# sch.net
KiCad netlist of a schematic drawn in Altium Designer
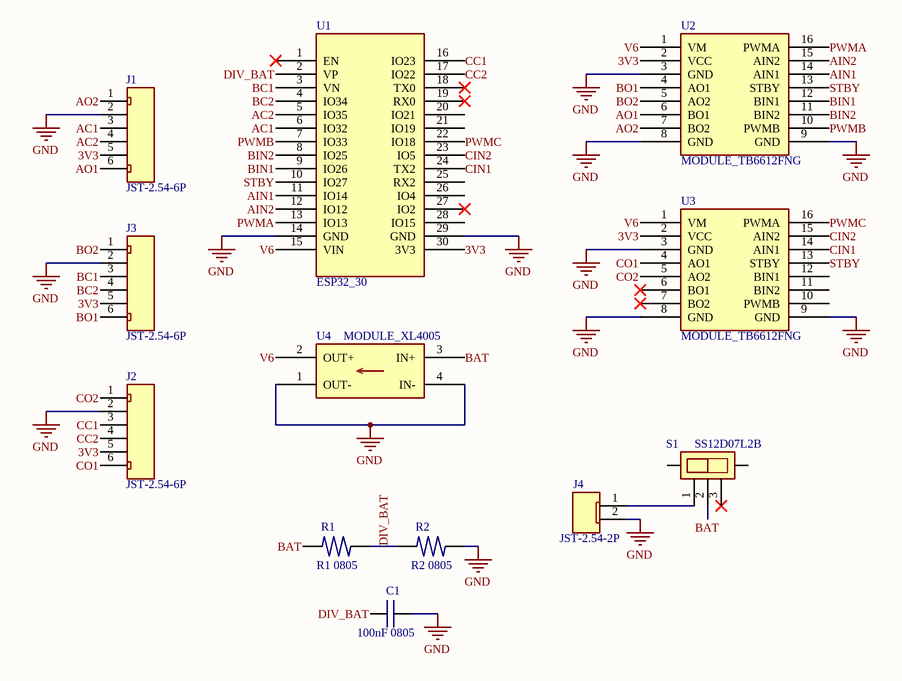
[diagram p0: sch.SchDoc]

(export (version "E")
  (design (tool "Eeschema 10.0.6"))
  (components
    (comp (ref "C1")
      (value "100nF 0805")
      (footprint "CAPACITOR 0805")
      (description "Generic Capacitor 0805, 2x1.25x1.4mm.")
      (libsource (lib "Ceramic Capacitor") (part "CAPACITOR 0805"))
    )
    (comp (ref "J1")
      (value "JST-2.54-6P")
      (footprint "JST-2.54-6P")
      (description "Female Connector JST 6 Vias, 2.54mm.")
      (libsource (lib "Connectors") (part "JST-2.54-6P"))
    )
    (comp (ref "J2")
      (value "JST-2.54-6P")
      (footprint "JST-2.54-6P")
      (description "Female Connector JST 6 Vias, 2.54mm.")
      (libsource (lib "Connectors") (part "JST-2.54-6P"))
    )
    (comp (ref "J3")
      (value "JST-2.54-6P")
      (footprint "JST-2.54-6P")
      (description "Female Connector JST 6 Vias, 2.54mm.")
      (libsource (lib "Connectors") (part "JST-2.54-6P"))
    )
    (comp (ref "J4")
      (value "JST-2.54-2P")
      (footprint "JST-2.54-2P")
      (description "Female Connector JST 2 Vias, 2.54mm.")
      (libsource (lib "Connectors") (part "JST-2.54-2P"))
    )
    (comp (ref "R1")
      (value "R1 0805")
      (footprint "RESISTOR_0805")
      (libsource (lib "Resistors") (part "RESISTOR_0805"))
    )
    (comp (ref "R2")
      (value "R2 0805")
      (footprint "RESISTOR_0805")
      (libsource (lib "Resistors") (part "RESISTOR_0805"))
    )
    (comp (ref "S1")
      (value "SS12D07L2B")
      (footprint "SS12D07L2B")
      (description "Vertical Slide Switch 5 Pins 8.7x4.5x4.7mm.")
      (libsource (lib "Buttons & Switches") (part "SS12D07L2B"))
    )
    (comp (ref "U1")
      (value "ESP32_30")
      (footprint "ESP32_30")
      (description "Microcontoller Board 30 Pins Wifi 2.4GHz BLE 4.2 ESP32-WROOM-32D")
      (libsource (lib "Espressif Microcontrollers") (part "ESP32_30"))
    )
    (comp (ref "U2")
      (value "MODULE_TB6612FNG")
      (footprint "MODULE_TB6612FNG")
      (description "Module Dual Motor Driver 2.5-13.5V 3.2A Peak 21x18mm")
      (libsource (lib "Motor Drivers") (part "MODULE_TB6612FNG"))
    )
    (comp (ref "U3")
      (value "MODULE_TB6612FNG")
      (footprint "MODULE_TB6612FNG")
      (description "Module Dual Motor Driver 2.5-13.5V 3.2A Peak 21x18mm")
      (libsource (lib "Motor Drivers") (part "MODULE_TB6612FNG"))
    )
    (comp (ref "U4")
      (value "MODULE_XL4005")
      (footprint "MODULE_XL4005")
      (description "MODULE BUCK STEP DOWN 5A 44x21mm")
      (libsource (lib "Voltage Regulators") (part "MODULE_XL4005"))
    )
  )
  (nets
    (net (code "1") (name "/3V3") (class "Default")
      (node (ref "J1") (pin "5") (pintype "passive"))
      (node (ref "J2") (pin "5") (pintype "passive"))
      (node (ref "J3") (pin "5") (pintype "passive"))
      (node (ref "U1") (pin "30") (pinfunction "3V3_30") (pintype "passive"))
      (node (ref "U2") (pin "2") (pinfunction "VCC_2") (pintype "passive"))
      (node (ref "U3") (pin "2") (pinfunction "VCC_2") (pintype "passive"))
    )
    (net (code "2") (name "/AC1") (class "Default")
      (node (ref "J1") (pin "3") (pintype "passive"))
      (node (ref "U1") (pin "6") (pinfunction "IO32_6") (pintype "passive"))
    )
    (net (code "3") (name "/AC2") (class "Default")
      (node (ref "J1") (pin "4") (pintype "passive"))
      (node (ref "U1") (pin "5") (pinfunction "IO35_5") (pintype "passive"))
    )
    (net (code "4") (name "/AIN1") (class "Default")
      (node (ref "U1") (pin "11") (pinfunction "IO14_11") (pintype "passive"))
      (node (ref "U2") (pin "14") (pinfunction "AIN1_14") (pintype "passive"))
    )
    (net (code "5") (name "/AIN2") (class "Default")
      (node (ref "U1") (pin "12") (pinfunction "IO12_12") (pintype "passive"))
      (node (ref "U2") (pin "15") (pinfunction "AIN2_15") (pintype "passive"))
    )
    (net (code "6") (name "/AO1") (class "Default")
      (node (ref "J1") (pin "6") (pintype "passive"))
      (node (ref "U2") (pin "6") (pinfunction "BO1_6") (pintype "passive"))
    )
    (net (code "7") (name "/AO2") (class "Default")
      (node (ref "J1") (pin "1") (pintype "passive"))
      (node (ref "U2") (pin "7") (pinfunction "BO2_7") (pintype "passive"))
    )
    (net (code "8") (name "/BAT") (class "Default")
      (node (ref "R1") (pin "2") (pinfunction "2_2") (pintype "passive"))
      (node (ref "S1") (pin "2") (pinfunction "2_2") (pintype "passive"))
      (node (ref "U4") (pin "3") (pinfunction "IN+_3") (pintype "passive"))
    )
    (net (code "9") (name "/BC1") (class "Default")
      (node (ref "J3") (pin "3") (pintype "passive"))
      (node (ref "U1") (pin "3") (pinfunction "VN_3") (pintype "passive"))
    )
    (net (code "10") (name "/BC2") (class "Default")
      (node (ref "J3") (pin "4") (pintype "passive"))
      (node (ref "U1") (pin "4") (pinfunction "IO34_4") (pintype "passive"))
    )
    (net (code "11") (name "/BIN1") (class "Default")
      (node (ref "U1") (pin "9") (pinfunction "IO26_9") (pintype "passive"))
      (node (ref "U2") (pin "12") (pinfunction "BIN1_12") (pintype "passive"))
    )
    (net (code "12") (name "/BIN2") (class "Default")
      (node (ref "U1") (pin "8") (pinfunction "IO25_8") (pintype "passive"))
      (node (ref "U2") (pin "11") (pinfunction "BIN2_11") (pintype "passive"))
    )
    (net (code "13") (name "/BO1") (class "Default")
      (node (ref "J3") (pin "6") (pintype "passive"))
      (node (ref "U2") (pin "4") (pinfunction "AO1_4") (pintype "passive"))
    )
    (net (code "14") (name "/BO2") (class "Default")
      (node (ref "J3") (pin "1") (pintype "passive"))
      (node (ref "U2") (pin "5") (pinfunction "AO2_5") (pintype "passive"))
    )
    (net (code "15") (name "/CC1") (class "Default")
      (node (ref "J2") (pin "3") (pintype "passive"))
      (node (ref "U1") (pin "16") (pinfunction "IO23_16") (pintype "passive"))
    )
    (net (code "16") (name "/CC2") (class "Default")
      (node (ref "J2") (pin "4") (pintype "passive"))
      (node (ref "U1") (pin "17") (pinfunction "IO22_17") (pintype "passive"))
    )
    (net (code "17") (name "/CIN1") (class "Default")
      (node (ref "U1") (pin "24") (pinfunction "TX2_24") (pintype "passive"))
      (node (ref "U3") (pin "14") (pinfunction "AIN1_14") (pintype "passive"))
    )
    (net (code "18") (name "/CIN2") (class "Default")
      (node (ref "U1") (pin "23") (pinfunction "IO5_23") (pintype "passive"))
      (node (ref "U3") (pin "15") (pinfunction "AIN2_15") (pintype "passive"))
    )
    (net (code "19") (name "/CO1") (class "Default")
      (node (ref "J2") (pin "6") (pintype "passive"))
      (node (ref "U3") (pin "4") (pinfunction "AO1_4") (pintype "passive"))
    )
    (net (code "20") (name "/CO2") (class "Default")
      (node (ref "J2") (pin "1") (pintype "passive"))
      (node (ref "U3") (pin "5") (pinfunction "AO2_5") (pintype "passive"))
    )
    (net (code "21") (name "/DIV_BAT") (class "Default")
      (node (ref "C1") (pin "1") (pinfunction "1_1") (pintype "passive"))
      (node (ref "R1") (pin "1") (pinfunction "1_1") (pintype "passive"))
      (node (ref "R2") (pin "2") (pinfunction "2_2") (pintype "passive"))
      (node (ref "U1") (pin "2") (pinfunction "VP_2") (pintype "passive"))
    )
    (net (code "22") (name "/PWMA") (class "Default")
      (node (ref "U1") (pin "13") (pinfunction "IO13_13") (pintype "passive"))
      (node (ref "U2") (pin "16") (pinfunction "PWMA_16") (pintype "passive"))
    )
    (net (code "23") (name "/PWMB") (class "Default")
      (node (ref "U1") (pin "7") (pinfunction "IO33_7") (pintype "passive"))
      (node (ref "U2") (pin "10") (pinfunction "PWMB_10") (pintype "passive"))
    )
    (net (code "24") (name "/PWMC") (class "Default")
      (node (ref "U1") (pin "22") (pinfunction "IO18_22") (pintype "passive"))
      (node (ref "U3") (pin "16") (pinfunction "PWMA_16") (pintype "passive"))
    )
    (net (code "25") (name "/STBY") (class "Default")
      (node (ref "U1") (pin "10") (pinfunction "IO27_10") (pintype "passive"))
      (node (ref "U2") (pin "13") (pinfunction "STBY_13") (pintype "passive"))
      (node (ref "U3") (pin "13") (pinfunction "STBY_13") (pintype "passive"))
    )
    (net (code "26") (name "/V6") (class "Default")
      (node (ref "U1") (pin "15") (pinfunction "VIN_15") (pintype "passive"))
      (node (ref "U2") (pin "1") (pinfunction "VM_1") (pintype "passive"))
      (node (ref "U3") (pin "1") (pinfunction "VM_1") (pintype "passive"))
      (node (ref "U4") (pin "2") (pinfunction "OUT+_2") (pintype "passive"))
    )
    (net (code "27") (name "GND") (class "Default")
      (node (ref "C1") (pin "2") (pinfunction "2_2") (pintype "passive"))
      (node (ref "J1") (pin "2") (pintype "passive"))
      (node (ref "J2") (pin "2") (pintype "passive"))
      (node (ref "J3") (pin "2") (pintype "passive"))
      (node (ref "J4") (pin "2") (pintype "passive"))
      (node (ref "R2") (pin "1") (pinfunction "1_1") (pintype "passive"))
      (node (ref "U1") (pin "14") (pinfunction "GND_14") (pintype "passive"))
      (node (ref "U1") (pin "29") (pinfunction "GND_29") (pintype "passive"))
      (node (ref "U2") (pin "3") (pinfunction "GND_3") (pintype "passive"))
      (node (ref "U2") (pin "8") (pinfunction "GND_8") (pintype "passive"))
      (node (ref "U2") (pin "9") (pinfunction "GND_9") (pintype "passive"))
      (node (ref "U3") (pin "3") (pinfunction "GND_3") (pintype "passive"))
      (node (ref "U3") (pin "8") (pinfunction "GND_8") (pintype "passive"))
      (node (ref "U3") (pin "9") (pinfunction "GND_9") (pintype "passive"))
      (node (ref "U4") (pin "1") (pinfunction "OUT-_1") (pintype "passive"))
      (node (ref "U4") (pin "4") (pinfunction "IN-_4") (pintype "passive"))
    )
    (net (code "28") (name "Net-(J4-Pad1)") (class "Default")
      (node (ref "J4") (pin "1") (pintype "passive"))
      (node (ref "S1") (pin "1") (pinfunction "1_1") (pintype "passive"))
    )
    (net (code "29") (name "unconnected-(S1-Pad3)") (class "Default")
      (node (ref "S1") (pin "3") (pinfunction "3_3") (pintype "passive+no_connect"))
    )
    (net (code "30") (name "unconnected-(U1-EN-Pad1)") (class "Default")
      (node (ref "U1") (pin "1") (pinfunction "EN_1") (pintype "passive+no_connect"))
    )
    (net (code "31") (name "unconnected-(U1-IO2-Pad27)") (class "Default")
      (node (ref "U1") (pin "27") (pinfunction "IO2_27") (pintype "passive+no_connect"))
    )
    (net (code "32") (name "unconnected-(U1-IO4-Pad26)") (class "Default")
      (node (ref "U1") (pin "26") (pinfunction "IO4_26") (pintype "passive"))
    )
    (net (code "33") (name "unconnected-(U1-IO15-Pad28)") (class "Default")
      (node (ref "U1") (pin "28") (pinfunction "IO15_28") (pintype "passive"))
    )
    (net (code "34") (name "unconnected-(U1-IO19-Pad21)") (class "Default")
      (node (ref "U1") (pin "21") (pinfunction "IO19_21") (pintype "passive"))
    )
    (net (code "35") (name "unconnected-(U1-IO21-Pad20)") (class "Default")
      (node (ref "U1") (pin "20") (pinfunction "IO21_20") (pintype "passive"))
    )
    (net (code "36") (name "unconnected-(U1-RX0-Pad19)") (class "Default")
      (node (ref "U1") (pin "19") (pinfunction "RX0_19") (pintype "passive+no_connect"))
    )
    (net (code "37") (name "unconnected-(U1-RX2-Pad25)") (class "Default")
      (node (ref "U1") (pin "25") (pinfunction "RX2_25") (pintype "passive"))
    )
    (net (code "38") (name "unconnected-(U1-TX0-Pad18)") (class "Default")
      (node (ref "U1") (pin "18") (pinfunction "TX0_18") (pintype "passive+no_connect"))
    )
    (net (code "39") (name "unconnected-(U3-BIN1-Pad12)") (class "Default")
      (node (ref "U3") (pin "12") (pinfunction "BIN1_12") (pintype "passive"))
    )
    (net (code "40") (name "unconnected-(U3-BIN2-Pad11)") (class "Default")
      (node (ref "U3") (pin "11") (pinfunction "BIN2_11") (pintype "passive"))
    )
    (net (code "41") (name "unconnected-(U3-BO1-Pad6)") (class "Default")
      (node (ref "U3") (pin "6") (pinfunction "BO1_6") (pintype "passive+no_connect"))
    )
    (net (code "42") (name "unconnected-(U3-BO2-Pad7)") (class "Default")
      (node (ref "U3") (pin "7") (pinfunction "BO2_7") (pintype "passive+no_connect"))
    )
    (net (code "43") (name "unconnected-(U3-PWMB-Pad10)") (class "Default")
      (node (ref "U3") (pin "10") (pinfunction "PWMB_10") (pintype "passive"))
    )
  )
)
